# emonPi2C_V1_1.net
KiCad netlist of a schematic drawn in EAGLE
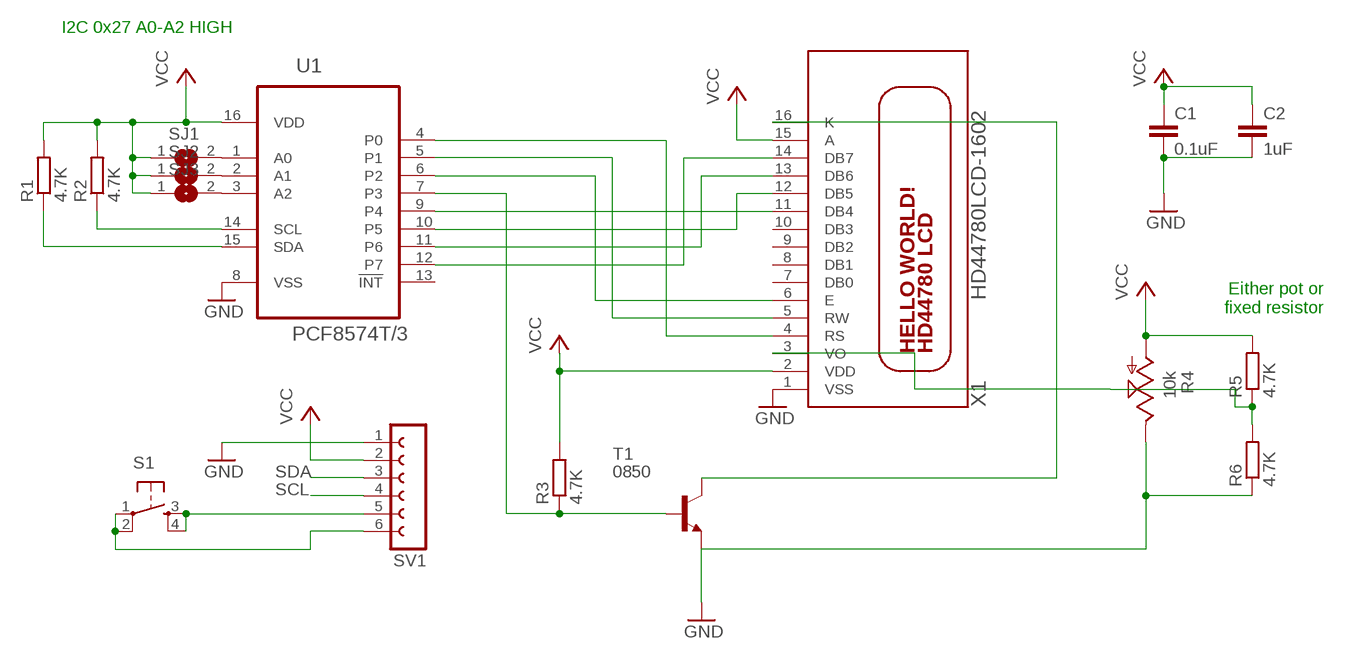
[diagram p0: schematic, sheet 1]

(export (version "E")
  (design (tool "Eeschema 10.0.6"))
  (components
    (comp (ref "C1")
      (value "0.1uF")
      (footprint "eagle-import:C0603")
      (libsource (lib "eagle-import") (part "C-EUC0603"))
    )
    (comp (ref "C2")
      (value "1uF")
      (footprint "eagle-import:C0603")
      (libsource (lib "eagle-import") (part "C-EUC0603"))
    )
    (comp (ref "R1")
      (value "4.7K")
      (footprint "eagle-import:R0603")
      (libsource (lib "eagle-import") (part "R-EU_R0603"))
    )
    (comp (ref "R2")
      (value "4.7K")
      (footprint "eagle-import:R0603")
      (libsource (lib "eagle-import") (part "R-EU_R0603"))
    )
    (comp (ref "R3")
      (value "4.7K")
      (footprint "eagle-import:R0603")
      (libsource (lib "eagle-import") (part "R-EU_R0603"))
    )
    (comp (ref "R4")
      (value "10k")
      (footprint "eagle-import:B25P")
      (libsource (lib "eagle-import") (part "TRIM_US-B25P"))
    )
    (comp (ref "R5")
      (value "4.7K")
      (footprint "eagle-import:R0603")
      (libsource (lib "eagle-import") (part "R-EU_R0603"))
    )
    (comp (ref "R6")
      (value "4.7K")
      (footprint "eagle-import:R0603")
      (libsource (lib "eagle-import") (part "R-EU_R0603"))
    )
    (comp (ref "S1")
      (value "TAC_SWITCHPTH")
      (footprint "eagle-import:TACTILE-PTH")
      (libsource (lib "eagle-import") (part "TAC_SWITCHPTH"))
    )
    (comp (ref "SJ1") (value "SJ") (footprint "eagle-import:SJ") (libsource (lib "eagle-import") (part "SJ")))
    (comp (ref "SJ2") (value "SJ") (footprint "eagle-import:SJ") (libsource (lib "eagle-import") (part "SJ")))
    (comp (ref "SJ3") (value "SJ") (footprint "eagle-import:SJ") (libsource (lib "eagle-import") (part "SJ")))
    (comp (ref "SV1")
      (value "FE06-1")
      (footprint "eagle-import:FE06")
      (libsource (lib "eagle-import") (part "FE06-1"))
    )
    (comp (ref "T1")
      (value "0850")
      (footprint "eagle-import:SOT23")
      (libsource (lib "eagle-import") (part "BCX70SMD"))
    )
    (comp (ref "U1")
      (value "PCF8574T/3")
      (footprint "eagle-import:SOIC127P1032X265-16N")
      (libsource (lib "eagle-import") (part "PCF8574T/3"))
    )
    (comp (ref "X1")
      (value "HD44780LCD-1602")
      (footprint "eagle-import:LCD1602")
      (libsource (lib "eagle-import") (part "HD44780LCD-1602"))
    )
  )
  (nets
    (net (code "1") (name "/SCL") (class "Default")
      (node (ref "R2") (pin "1") (pinfunction "1_1") (pintype "passive"))
      (node (ref "SV1") (pin "4") (pinfunction "4_4") (pintype "passive"))
      (node (ref "U1") (pin "14") (pinfunction "SCL_14") (pintype "passive"))
    )
    (net (code "2") (name "/SDA") (class "Default")
      (node (ref "R1") (pin "1") (pinfunction "1_1") (pintype "passive"))
      (node (ref "SV1") (pin "3") (pinfunction "3_3") (pintype "passive"))
      (node (ref "U1") (pin "15") (pinfunction "SDA_15") (pintype "passive"))
    )
    (net (code "3") (name "GND") (class "Default")
      (node (ref "C1") (pin "2") (pinfunction "2_2") (pintype "passive"))
      (node (ref "C2") (pin "2") (pinfunction "2_2") (pintype "passive"))
      (node (ref "R4") (pin "E") (pinfunction "E_E") (pintype "passive"))
      (node (ref "R6") (pin "1") (pinfunction "1_1") (pintype "passive"))
      (node (ref "SV1") (pin "1") (pinfunction "1_1") (pintype "passive"))
      (node (ref "T1") (pin "2") (pinfunction "E_2") (pintype "passive"))
      (node (ref "U1") (pin "8") (pinfunction "VSS_8") (pintype "power_in"))
      (node (ref "X1") (pin "1") (pinfunction "VSS_1") (pintype "power_in"))
    )
    (net (code "4") (name "Net-(S1-Pad1)") (class "Default")
      (node (ref "S1") (pin "1") (pinfunction "1_1") (pintype "passive"))
      (node (ref "S1") (pin "2") (pinfunction "2_2") (pintype "passive"))
      (node (ref "SV1") (pin "6") (pinfunction "6_6") (pintype "passive"))
    )
    (net (code "5") (name "Net-(S1-Pad3)") (class "Default")
      (node (ref "S1") (pin "3") (pinfunction "3_3") (pintype "passive"))
      (node (ref "S1") (pin "4") (pinfunction "4_4") (pintype "passive"))
      (node (ref "SV1") (pin "5") (pinfunction "5_5") (pintype "passive"))
    )
    (net (code "6") (name "Net-(T1-B)") (class "Default")
      (node (ref "R3") (pin "1") (pinfunction "1_1") (pintype "passive"))
      (node (ref "T1") (pin "1") (pinfunction "B_1") (pintype "passive"))
      (node (ref "U1") (pin "7") (pinfunction "P3_7") (pintype "bidirectional"))
    )
    (net (code "7") (name "Net-(T1-C)") (class "Default")
      (node (ref "T1") (pin "3") (pinfunction "C_3") (pintype "passive"))
      (node (ref "X1") (pin "16") (pinfunction "K_16") (pintype "input"))
    )
    (net (code "8") (name "Net-(U1-A0)") (class "Default")
      (node (ref "SJ1") (pin "2") (pinfunction "2_2") (pintype "passive"))
      (node (ref "U1") (pin "1") (pinfunction "A0_1") (pintype "input"))
    )
    (net (code "9") (name "Net-(U1-A1)") (class "Default")
      (node (ref "SJ2") (pin "2") (pinfunction "2_2") (pintype "passive"))
      (node (ref "U1") (pin "2") (pinfunction "A1_2") (pintype "input"))
    )
    (net (code "10") (name "Net-(U1-A2)") (class "Default")
      (node (ref "SJ3") (pin "2") (pinfunction "2_2") (pintype "passive"))
      (node (ref "U1") (pin "3") (pinfunction "A2_3") (pintype "input"))
    )
    (net (code "11") (name "Net-(U1-P0)") (class "Default")
      (node (ref "U1") (pin "4") (pinfunction "P0_4") (pintype "bidirectional"))
      (node (ref "X1") (pin "4") (pinfunction "RS_4") (pintype "input"))
    )
    (net (code "12") (name "Net-(U1-P1)") (class "Default")
      (node (ref "U1") (pin "5") (pinfunction "P1_5") (pintype "bidirectional"))
      (node (ref "X1") (pin "5") (pinfunction "RW_5") (pintype "input"))
    )
    (net (code "13") (name "Net-(U1-P2)") (class "Default")
      (node (ref "U1") (pin "6") (pinfunction "P2_6") (pintype "bidirectional"))
      (node (ref "X1") (pin "6") (pinfunction "E_6") (pintype "input"))
    )
    (net (code "14") (name "Net-(U1-P4)") (class "Default")
      (node (ref "U1") (pin "9") (pinfunction "P4_9") (pintype "bidirectional"))
      (node (ref "X1") (pin "11") (pinfunction "DB4_11") (pintype "bidirectional"))
    )
    (net (code "15") (name "Net-(U1-P5)") (class "Default")
      (node (ref "U1") (pin "10") (pinfunction "P5_10") (pintype "bidirectional"))
      (node (ref "X1") (pin "12") (pinfunction "DB5_12") (pintype "bidirectional"))
    )
    (net (code "16") (name "Net-(U1-P6)") (class "Default")
      (node (ref "U1") (pin "11") (pinfunction "P6_11") (pintype "bidirectional"))
      (node (ref "X1") (pin "13") (pinfunction "DB6_13") (pintype "bidirectional"))
    )
    (net (code "17") (name "Net-(U1-P7)") (class "Default")
      (node (ref "U1") (pin "12") (pinfunction "P7_12") (pintype "bidirectional"))
      (node (ref "X1") (pin "14") (pinfunction "DB7_14") (pintype "bidirectional"))
    )
    (net (code "18") (name "Net-(X1-VO)") (class "Default")
      (node (ref "R4") (pin "S") (pinfunction "S_S") (pintype "passive"))
      (node (ref "R5") (pin "1") (pinfunction "1_1") (pintype "passive"))
      (node (ref "R6") (pin "2") (pinfunction "2_2") (pintype "passive"))
      (node (ref "X1") (pin "3") (pinfunction "VO_3") (pintype "input"))
    )
    (net (code "19") (name "VCC") (class "Default")
      (node (ref "C1") (pin "1") (pinfunction "1_1") (pintype "passive"))
      (node (ref "C2") (pin "1") (pinfunction "1_1") (pintype "passive"))
      (node (ref "R1") (pin "2") (pinfunction "2_2") (pintype "passive"))
      (node (ref "R2") (pin "2") (pinfunction "2_2") (pintype "passive"))
      (node (ref "R3") (pin "2") (pinfunction "2_2") (pintype "passive"))
      (node (ref "R4") (pin "A") (pinfunction "A_A") (pintype "passive"))
      (node (ref "R5") (pin "2") (pinfunction "2_2") (pintype "passive"))
      (node (ref "SJ1") (pin "1") (pinfunction "1_1") (pintype "passive"))
      (node (ref "SJ2") (pin "1") (pinfunction "1_1") (pintype "passive"))
      (node (ref "SJ3") (pin "1") (pinfunction "1_1") (pintype "passive"))
      (node (ref "SV1") (pin "2") (pinfunction "2_2") (pintype "passive"))
      (node (ref "U1") (pin "16") (pinfunction "VDD_16") (pintype "power_in"))
      (node (ref "X1") (pin "15") (pinfunction "A_15") (pintype "input"))
      (node (ref "X1") (pin "2") (pinfunction "VDD_2") (pintype "power_in"))
    )
    (net (code "20") (name "unconnected-(U1-~{INT}-Pad13)") (class "Default")
      (node (ref "U1") (pin "13") (pinfunction "~{INT}_13") (pintype "output"))
    )
    (net (code "21") (name "unconnected-(X1-DB0-Pad7)") (class "Default")
      (node (ref "X1") (pin "7") (pinfunction "DB0_7") (pintype "bidirectional"))
    )
    (net (code "22") (name "unconnected-(X1-DB1-Pad8)") (class "Default")
      (node (ref "X1") (pin "8") (pinfunction "DB1_8") (pintype "bidirectional"))
    )
    (net (code "23") (name "unconnected-(X1-DB2-Pad9)") (class "Default")
      (node (ref "X1") (pin "9") (pinfunction "DB2_9") (pintype "bidirectional"))
    )
    (net (code "24") (name "unconnected-(X1-DB3-Pad10)") (class "Default")
      (node (ref "X1") (pin "10") (pinfunction "DB3_10") (pintype "bidirectional"))
    )
  )
)
